# 11_-_PERIPHERALS_D.net
KiCad netlist of a schematic drawn in Altium Designer
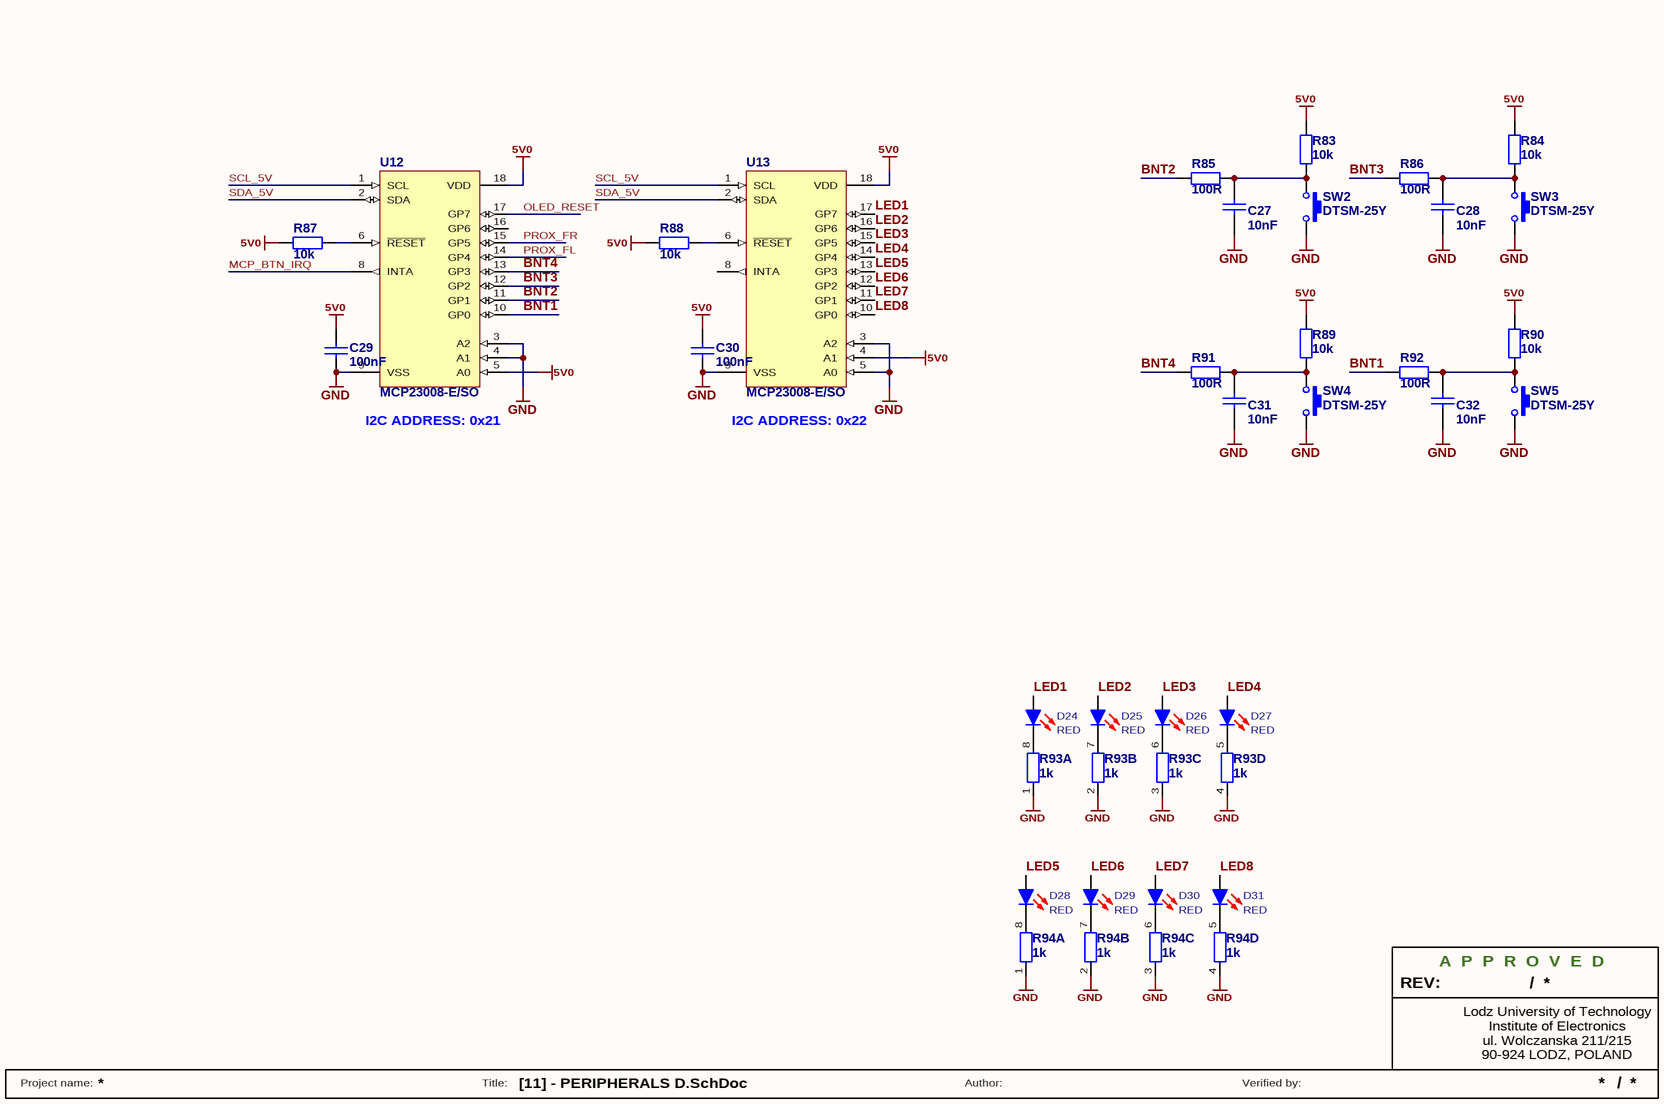
[diagram p0: [11] - PERIPHERALS D.SchDoc]

(export (version "E")
  (design (tool "Eeschema 10.0.6"))
  (components
    (comp (ref "C27")
      (value "10nF")
      (footprint "C0805")
      (description "Capacitor")
      (libsource (lib "capacitors") (part "Cap"))
    )
    (comp (ref "C28")
      (value "10nF")
      (footprint "C0805")
      (description "Capacitor")
      (libsource (lib "capacitors") (part "Cap"))
    )
    (comp (ref "C29")
      (value "100nF")
      (footprint "C0805")
      (description "Capacitor")
      (libsource (lib "") (part "Cap_1"))
    )
    (comp (ref "C30")
      (value "100nF")
      (footprint "C0805")
      (description "Capacitor")
      (libsource (lib "") (part "Cap_1"))
    )
    (comp (ref "C31")
      (value "10nF")
      (footprint "C0805")
      (description "Capacitor")
      (libsource (lib "capacitors") (part "Cap"))
    )
    (comp (ref "C32")
      (value "10nF")
      (footprint "C0805")
      (description "Capacitor")
      (libsource (lib "capacitors") (part "Cap"))
    )
    (comp (ref "D24")
      (value "RED")
      (footprint "LED0805R")
      (description "RED LED")
      (libsource (lib "leds") (part "LED_RED"))
    )
    (comp (ref "D25")
      (value "RED")
      (footprint "LED0805R")
      (description "RED LED")
      (libsource (lib "leds") (part "LED_RED"))
    )
    (comp (ref "D26")
      (value "RED")
      (footprint "LED0805R")
      (description "RED LED")
      (libsource (lib "leds") (part "LED_RED"))
    )
    (comp (ref "D27")
      (value "RED")
      (footprint "LED0805R")
      (description "RED LED")
      (libsource (lib "leds") (part "LED_RED"))
    )
    (comp (ref "D28")
      (value "RED")
      (footprint "LED0805R")
      (description "RED LED")
      (libsource (lib "leds") (part "LED_RED"))
    )
    (comp (ref "D29")
      (value "RED")
      (footprint "LED0805R")
      (description "RED LED")
      (libsource (lib "leds") (part "LED_RED"))
    )
    (comp (ref "D30")
      (value "RED")
      (footprint "LED0805R")
      (description "RED LED")
      (libsource (lib "leds") (part "LED_RED"))
    )
    (comp (ref "D31")
      (value "RED")
      (footprint "LED0805R")
      (description "RED LED")
      (libsource (lib "leds") (part "LED_RED"))
    )
    (comp (ref "R83")
      (value "10k")
      (footprint "R0805")
      (description "Resistor")
      (libsource (lib "") (part "Res_1"))
    )
    (comp (ref "R84")
      (value "10k")
      (footprint "R0805")
      (description "Resistor")
      (libsource (lib "") (part "Res_1"))
    )
    (comp (ref "R85")
      (value "100R")
      (footprint "R0805")
      (description "Resistor")
      (libsource (lib "resistors") (part "Res"))
    )
    (comp (ref "R86")
      (value "100R")
      (footprint "R0805")
      (description "Resistor")
      (libsource (lib "resistors") (part "Res"))
    )
    (comp (ref "R87")
      (value "10k")
      (footprint "R0805")
      (description "Resistor")
      (libsource (lib "") (part "Res_2"))
    )
    (comp (ref "R88")
      (value "10k")
      (footprint "R0805")
      (description "Resistor")
      (libsource (lib "") (part "Res_2"))
    )
    (comp (ref "R89")
      (value "10k")
      (footprint "R0805")
      (description "Resistor")
      (libsource (lib "") (part "Res_1"))
    )
    (comp (ref "R90")
      (value "10k")
      (footprint "R0805")
      (description "Resistor")
      (libsource (lib "") (part "Res_1"))
    )
    (comp (ref "R91")
      (value "100R")
      (footprint "R0805")
      (description "Resistor")
      (libsource (lib "resistors") (part "Res"))
    )
    (comp (ref "R92")
      (value "100R")
      (footprint "R0805")
      (description "Resistor")
      (libsource (lib "resistors") (part "Res"))
    )
    (comp (ref "R93")
      (value "1k")
      (footprint "RPack_0603x4_1206")
      (description "Isolated Resistor Network - Parts")
      (fields (field (name "PUBLISHER") "Altium Limited"))
      (libsource (lib "resistors") (part "Res Pack4_1"))
    )
    (comp (ref "R94")
      (value "1k")
      (footprint "RPack_0603x4_1206")
      (description "Isolated Resistor Network - Parts")
      (fields (field (name "PUBLISHER") "Altium Limited"))
      (libsource (lib "resistors") (part "Res Pack4_1"))
    )
    (comp (ref "SW2")
      (value "DTSM-25Y")
      (footprint "DTSM-25Y")
      (description "DIPTRONICS Yellow 12x12mm SMD Tactile SPST-NO Switch")
      (libsource (lib "microswitches") (part "DTSM-25Y"))
    )
    (comp (ref "SW3")
      (value "DTSM-25Y")
      (footprint "DTSM-25Y")
      (description "DIPTRONICS Yellow 12x12mm SMD Tactile SPST-NO Switch")
      (libsource (lib "microswitches") (part "DTSM-25Y"))
    )
    (comp (ref "SW4")
      (value "DTSM-25Y")
      (footprint "DTSM-25Y")
      (description "DIPTRONICS Yellow 12x12mm SMD Tactile SPST-NO Switch")
      (libsource (lib "microswitches") (part "DTSM-25Y"))
    )
    (comp (ref "SW5")
      (value "DTSM-25Y")
      (footprint "DTSM-25Y")
      (description "DIPTRONICS Yellow 12x12mm SMD Tactile SPST-NO Switch")
      (libsource (lib "microswitches") (part "DTSM-25Y"))
    )
    (comp (ref "U12")
      (value "MCP23008-E/SO")
      (footprint "SO18W")
      (description "8-Bit I/O Expander with Serial Interface I2C, 18-Pin SOIC Package")
      (libsource (lib "io_expanders") (part "MCP23008-E/SO"))
    )
    (comp (ref "U13")
      (value "MCP23008-E/SO")
      (footprint "SO18W")
      (description "8-Bit I/O Expander with Serial Interface I2C, 18-Pin SOIC Package")
      (libsource (lib "io_expanders") (part "MCP23008-E/SO"))
    )
  )
  (nets
    (net (code "1") (name "/BNT1") (class "Default")
      (node (ref "R92") (pin "1") (pinfunction "1_1") (pintype "passive"))
      (node (ref "U12") (pin "10") (pinfunction "GP0_10") (pintype "bidirectional"))
    )
    (net (code "2") (name "/BNT2") (class "Default")
      (node (ref "R85") (pin "1") (pinfunction "1_1") (pintype "passive"))
      (node (ref "U12") (pin "11") (pinfunction "GP1_11") (pintype "bidirectional"))
    )
    (net (code "3") (name "/BNT3") (class "Default")
      (node (ref "R86") (pin "1") (pinfunction "1_1") (pintype "passive"))
      (node (ref "U12") (pin "12") (pinfunction "GP2_12") (pintype "bidirectional"))
    )
    (net (code "4") (name "/BNT4") (class "Default")
      (node (ref "R91") (pin "1") (pinfunction "1_1") (pintype "passive"))
      (node (ref "U12") (pin "13") (pinfunction "GP3_13") (pintype "bidirectional"))
    )
    (net (code "5") (name "/LED1") (class "Default")
      (node (ref "D24") (pin "1") (pinfunction "A_1") (pintype "passive"))
      (node (ref "U13") (pin "17") (pinfunction "GP7_17") (pintype "bidirectional"))
    )
    (net (code "6") (name "/LED2") (class "Default")
      (node (ref "D25") (pin "1") (pinfunction "A_1") (pintype "passive"))
      (node (ref "U13") (pin "16") (pinfunction "GP6_16") (pintype "bidirectional"))
    )
    (net (code "7") (name "/LED3") (class "Default")
      (node (ref "D26") (pin "1") (pinfunction "A_1") (pintype "passive"))
      (node (ref "U13") (pin "15") (pinfunction "GP5_15") (pintype "bidirectional"))
    )
    (net (code "8") (name "/LED4") (class "Default")
      (node (ref "D27") (pin "1") (pinfunction "A_1") (pintype "passive"))
      (node (ref "U13") (pin "14") (pinfunction "GP4_14") (pintype "bidirectional"))
    )
    (net (code "9") (name "/LED5") (class "Default")
      (node (ref "D28") (pin "1") (pinfunction "A_1") (pintype "passive"))
      (node (ref "U13") (pin "13") (pinfunction "GP3_13") (pintype "bidirectional"))
    )
    (net (code "10") (name "/LED6") (class "Default")
      (node (ref "D29") (pin "1") (pinfunction "A_1") (pintype "passive"))
      (node (ref "U13") (pin "12") (pinfunction "GP2_12") (pintype "bidirectional"))
    )
    (net (code "11") (name "/LED7") (class "Default")
      (node (ref "D30") (pin "1") (pinfunction "A_1") (pintype "passive"))
      (node (ref "U13") (pin "11") (pinfunction "GP1_11") (pintype "bidirectional"))
    )
    (net (code "12") (name "/LED8") (class "Default")
      (node (ref "D31") (pin "1") (pinfunction "A_1") (pintype "passive"))
      (node (ref "U13") (pin "10") (pinfunction "GP0_10") (pintype "bidirectional"))
    )
    (net (code "13") (name "/MCP_BTN_IRQ") (class "Default")
      (node (ref "U12") (pin "8") (pinfunction "INTA_8") (pintype "output"))
    )
    (net (code "14") (name "/OLED_RESET") (class "Default")
      (node (ref "U12") (pin "17") (pinfunction "GP7_17") (pintype "bidirectional"))
    )
    (net (code "15") (name "/PROX_FL") (class "Default")
      (node (ref "U12") (pin "14") (pinfunction "GP4_14") (pintype "bidirectional"))
    )
    (net (code "16") (name "/PROX_FR") (class "Default")
      (node (ref "U12") (pin "15") (pinfunction "GP5_15") (pintype "bidirectional"))
    )
    (net (code "17") (name "/SCL_5V") (class "Default")
      (node (ref "U12") (pin "1") (pinfunction "SCL_1") (pintype "input"))
      (node (ref "U13") (pin "1") (pinfunction "SCL_1") (pintype "input"))
    )
    (net (code "18") (name "/SDA_5V") (class "Default")
      (node (ref "U12") (pin "2") (pinfunction "SDA_2") (pintype "bidirectional"))
      (node (ref "U13") (pin "2") (pinfunction "SDA_2") (pintype "bidirectional"))
    )
    (net (code "19") (name "5V0") (class "Default")
      (node (ref "C29") (pin "2") (pinfunction "2_2") (pintype "passive"))
      (node (ref "C30") (pin "2") (pinfunction "2_2") (pintype "passive"))
      (node (ref "R83") (pin "2") (pinfunction "2_2") (pintype "passive"))
      (node (ref "R84") (pin "2") (pinfunction "2_2") (pintype "passive"))
      (node (ref "R87") (pin "1") (pinfunction "1_1") (pintype "passive"))
      (node (ref "R88") (pin "1") (pinfunction "1_1") (pintype "passive"))
      (node (ref "R89") (pin "2") (pinfunction "2_2") (pintype "passive"))
      (node (ref "R90") (pin "2") (pinfunction "2_2") (pintype "passive"))
      (node (ref "U12") (pin "18") (pinfunction "VDD_18") (pintype "power_in"))
      (node (ref "U12") (pin "5") (pinfunction "A0_5") (pintype "input"))
      (node (ref "U13") (pin "18") (pinfunction "VDD_18") (pintype "power_in"))
      (node (ref "U13") (pin "4") (pinfunction "A1_4") (pintype "input"))
    )
    (net (code "20") (name "GND") (class "Default")
      (node (ref "C27") (pin "1") (pinfunction "1_1") (pintype "passive"))
      (node (ref "C28") (pin "1") (pinfunction "1_1") (pintype "passive"))
      (node (ref "C29") (pin "1") (pinfunction "1_1") (pintype "passive"))
      (node (ref "C30") (pin "1") (pinfunction "1_1") (pintype "passive"))
      (node (ref "C31") (pin "1") (pinfunction "1_1") (pintype "passive"))
      (node (ref "C32") (pin "1") (pinfunction "1_1") (pintype "passive"))
      (node (ref "R93") (pin "1") (pinfunction "1_1") (pintype "passive"))
      (node (ref "R93") (pin "2") (pinfunction "2_2") (pintype "passive"))
      (node (ref "R93") (pin "3") (pinfunction "3_3") (pintype "passive"))
      (node (ref "R93") (pin "4") (pinfunction "4_4") (pintype "passive"))
      (node (ref "R94") (pin "1") (pinfunction "1_1") (pintype "passive"))
      (node (ref "R94") (pin "2") (pinfunction "2_2") (pintype "passive"))
      (node (ref "R94") (pin "3") (pinfunction "3_3") (pintype "passive"))
      (node (ref "R94") (pin "4") (pinfunction "4_4") (pintype "passive"))
      (node (ref "SW2") (pin "2") (pinfunction "2_2") (pintype "passive"))
      (node (ref "SW3") (pin "2") (pinfunction "2_2") (pintype "passive"))
      (node (ref "SW4") (pin "2") (pinfunction "2_2") (pintype "passive"))
      (node (ref "SW5") (pin "2") (pinfunction "2_2") (pintype "passive"))
      (node (ref "U12") (pin "3") (pinfunction "A2_3") (pintype "input"))
      (node (ref "U12") (pin "4") (pinfunction "A1_4") (pintype "input"))
      (node (ref "U12") (pin "9") (pinfunction "VSS_9") (pintype "power_in"))
      (node (ref "U13") (pin "3") (pinfunction "A2_3") (pintype "input"))
      (node (ref "U13") (pin "5") (pinfunction "A0_5") (pintype "input"))
      (node (ref "U13") (pin "9") (pinfunction "VSS_9") (pintype "power_in"))
    )
    (net (code "21") (name "Net-(C27-Pad2)") (class "Default")
      (node (ref "C27") (pin "2") (pinfunction "2_2") (pintype "passive"))
      (node (ref "R83") (pin "1") (pinfunction "1_1") (pintype "passive"))
      (node (ref "R85") (pin "2") (pinfunction "2_2") (pintype "passive"))
      (node (ref "SW2") (pin "1") (pinfunction "1_1") (pintype "passive"))
    )
    (net (code "22") (name "Net-(C28-Pad2)") (class "Default")
      (node (ref "C28") (pin "2") (pinfunction "2_2") (pintype "passive"))
      (node (ref "R84") (pin "1") (pinfunction "1_1") (pintype "passive"))
      (node (ref "R86") (pin "2") (pinfunction "2_2") (pintype "passive"))
      (node (ref "SW3") (pin "1") (pinfunction "1_1") (pintype "passive"))
    )
    (net (code "23") (name "Net-(C31-Pad2)") (class "Default")
      (node (ref "C31") (pin "2") (pinfunction "2_2") (pintype "passive"))
      (node (ref "R89") (pin "1") (pinfunction "1_1") (pintype "passive"))
      (node (ref "R91") (pin "2") (pinfunction "2_2") (pintype "passive"))
      (node (ref "SW4") (pin "1") (pinfunction "1_1") (pintype "passive"))
    )
    (net (code "24") (name "Net-(C32-Pad2)") (class "Default")
      (node (ref "C32") (pin "2") (pinfunction "2_2") (pintype "passive"))
      (node (ref "R90") (pin "1") (pinfunction "1_1") (pintype "passive"))
      (node (ref "R92") (pin "2") (pinfunction "2_2") (pintype "passive"))
      (node (ref "SW5") (pin "1") (pinfunction "1_1") (pintype "passive"))
    )
    (net (code "25") (name "Net-(D24-K)") (class "Default")
      (node (ref "D24") (pin "2") (pinfunction "K_2") (pintype "passive"))
      (node (ref "R93") (pin "8") (pinfunction "8_8") (pintype "passive"))
    )
    (net (code "26") (name "Net-(D25-K)") (class "Default")
      (node (ref "D25") (pin "2") (pinfunction "K_2") (pintype "passive"))
      (node (ref "R93") (pin "7") (pinfunction "7_7") (pintype "passive"))
    )
    (net (code "27") (name "Net-(D26-K)") (class "Default")
      (node (ref "D26") (pin "2") (pinfunction "K_2") (pintype "passive"))
      (node (ref "R93") (pin "6") (pinfunction "6_6") (pintype "passive"))
    )
    (net (code "28") (name "Net-(D27-K)") (class "Default")
      (node (ref "D27") (pin "2") (pinfunction "K_2") (pintype "passive"))
      (node (ref "R93") (pin "5") (pinfunction "5_5") (pintype "passive"))
    )
    (net (code "29") (name "Net-(D28-K)") (class "Default")
      (node (ref "D28") (pin "2") (pinfunction "K_2") (pintype "passive"))
      (node (ref "R94") (pin "8") (pinfunction "8_8") (pintype "passive"))
    )
    (net (code "30") (name "Net-(D29-K)") (class "Default")
      (node (ref "D29") (pin "2") (pinfunction "K_2") (pintype "passive"))
      (node (ref "R94") (pin "7") (pinfunction "7_7") (pintype "passive"))
    )
    (net (code "31") (name "Net-(D30-K)") (class "Default")
      (node (ref "D30") (pin "2") (pinfunction "K_2") (pintype "passive"))
      (node (ref "R94") (pin "6") (pinfunction "6_6") (pintype "passive"))
    )
    (net (code "32") (name "Net-(D31-K)") (class "Default")
      (node (ref "D31") (pin "2") (pinfunction "K_2") (pintype "passive"))
      (node (ref "R94") (pin "5") (pinfunction "5_5") (pintype "passive"))
    )
    (net (code "33") (name "Net-(U12-~{RESET})") (class "Default")
      (node (ref "R87") (pin "2") (pinfunction "2_2") (pintype "passive"))
      (node (ref "U12") (pin "6") (pinfunction "~{RESET}_6") (pintype "input"))
    )
    (net (code "34") (name "Net-(U13-~{RESET})") (class "Default")
      (node (ref "R88") (pin "2") (pinfunction "2_2") (pintype "passive"))
      (node (ref "U13") (pin "6") (pinfunction "~{RESET}_6") (pintype "input"))
    )
    (net (code "35") (name "unconnected-(U12-GP6-Pad16)") (class "Default")
      (node (ref "U12") (pin "16") (pinfunction "GP6_16") (pintype "bidirectional"))
    )
    (net (code "36") (name "unconnected-(U13-INTA-Pad8)") (class "Default")
      (node (ref "U13") (pin "8") (pinfunction "INTA_8") (pintype "output"))
    )
  )
)
